# RTC_Miscellaneous.net
KiCad netlist of a schematic drawn in Altium Designer
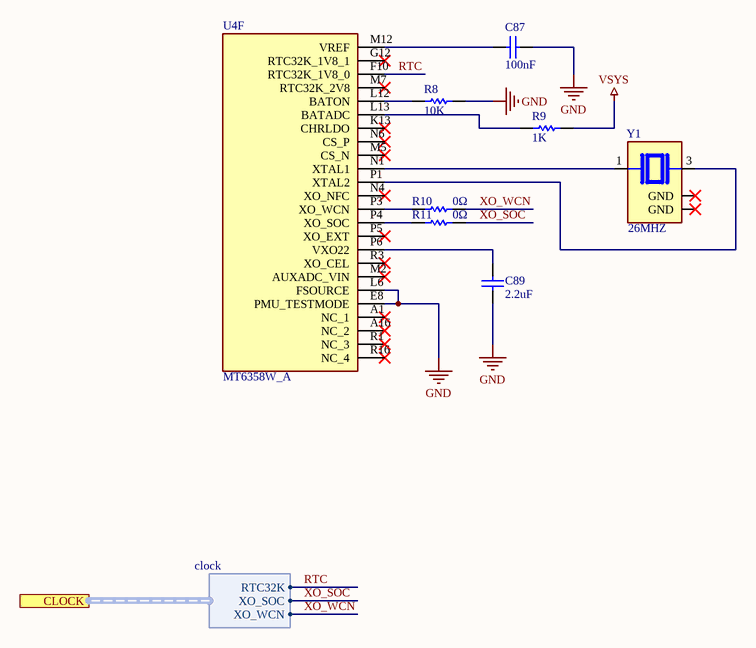
[diagram p0: RTC_Miscellaneous.SchDoc]

(export (version "E")
  (design (tool "Eeschema 10.0.6"))
  (components
    (comp (ref "C87")
      (value "100nF")
      (footprint "C0603")
      (fields (field (name "Comment") "C0603"))
      (libsource (lib "kit") (part "C0603"))
    )
    (comp (ref "C89")
      (value "2.2uF")
      (footprint "C0805")
      (fields (field (name "Comment") "C0805"))
      (libsource (lib "kit") (part "C0805"))
    )
    (comp (ref "R8")
      (value "10K")
      (footprint "R0603")
      (fields (field (name "Comment") "R0603"))
      (libsource (lib "kit") (part "R0603"))
    )
    (comp (ref "R9")
      (value "1K")
      (footprint "R0603")
      (fields (field (name "Comment") "R0603"))
      (libsource (lib "kit") (part "R0603"))
    )
    (comp (ref "R10")
      (value "0Ω")
      (footprint "R0603")
      (fields (field (name "Comment") "R0603"))
      (libsource (lib "kit") (part "R0603"))
    )
    (comp (ref "R11")
      (value "0Ω")
      (footprint "R0603")
      (fields (field (name "Comment") "R0603"))
      (libsource (lib "kit") (part "R0603"))
    )
    (comp (ref "U4")
      (value "MT6358W_A")
      (footprint "BGA194C40P16X15_640X600X66")
      (description "PMIC")
      (fields
        (field (name "MANUFACTURER_PART_NUMBER") "MT6358W/A")
        (field (name "MOUSER PART NUMBER") "840-MT6358W/A")
      )
      (libsource (lib "kit") (part "MT6358W_A"))
    )
    (comp (ref "Y1")
      (value "26MHZ")
      (footprint "OSCCC320X250X90N")
      (libsource (lib "kit") (part "NX3225GA-26MHZ-TI"))
    )
  )
  (nets
    (net (code "2") (name "/RTC") (class "Default")
      (node (ref "U4") (pin "F10") (pinfunction "RTC32K_1V8_0_F10") (pintype "passive"))
    )
    (net (code "3") (name "/XO_SOC") (class "Default")
      (node (ref "R11") (pin "2") (pinfunction "2_2") (pintype "passive"))
    )
    (net (code "4") (name "/XO_WCN") (class "Default")
      (node (ref "R10") (pin "2") (pinfunction "2_2") (pintype "passive"))
    )
    (net (code "6") (name "GND") (class "Default")
      (node (ref "C87") (pin "1") (pinfunction "1_1") (pintype "passive"))
      (node (ref "C89") (pin "1") (pinfunction "1_1") (pintype "passive"))
      (node (ref "R8") (pin "2") (pinfunction "2_2") (pintype "passive"))
      (node (ref "U4") (pin "E8") (pinfunction "PMU_TESTMODE_E8") (pintype "passive"))
      (node (ref "U4") (pin "L6") (pinfunction "FSOURCE_L6") (pintype "passive"))
    )
    (net (code "7") (name "Net-(U4F-BATADC)") (class "Default")
      (node (ref "R9") (pin "1") (pinfunction "1_1") (pintype "passive"))
      (node (ref "U4") (pin "L13") (pinfunction "BATADC_L13") (pintype "passive"))
    )
    (net (code "8") (name "Net-(U4F-BATON)") (class "Default")
      (node (ref "R8") (pin "1") (pinfunction "1_1") (pintype "passive"))
      (node (ref "U4") (pin "L12") (pinfunction "BATON_L12") (pintype "passive"))
    )
    (net (code "9") (name "Net-(U4F-VREF)") (class "Default")
      (node (ref "C87") (pin "2") (pinfunction "2_2") (pintype "passive"))
      (node (ref "U4") (pin "M12") (pinfunction "VREF_M12") (pintype "passive"))
    )
    (net (code "10") (name "Net-(U4F-VXO22)") (class "Default")
      (node (ref "C89") (pin "2") (pinfunction "2_2") (pintype "passive"))
      (node (ref "U4") (pin "P6") (pinfunction "VXO22_P6") (pintype "passive"))
    )
    (net (code "11") (name "Net-(U4F-XO_SOC)") (class "Default")
      (node (ref "R11") (pin "1") (pinfunction "1_1") (pintype "passive"))
      (node (ref "U4") (pin "P4") (pinfunction "XO_SOC_P4") (pintype "passive"))
    )
    (net (code "12") (name "Net-(U4F-XO_WCN)") (class "Default")
      (node (ref "R10") (pin "1") (pinfunction "1_1") (pintype "passive"))
      (node (ref "U4") (pin "P3") (pinfunction "XO_WCN_P3") (pintype "passive"))
    )
    (net (code "13") (name "Net-(U4F-XTAL1)") (class "Default")
      (node (ref "U4") (pin "N1") (pinfunction "XTAL1_N1") (pintype "passive"))
      (node (ref "Y1") (pin "1") (pinfunction "1_1") (pintype "passive"))
    )
    (net (code "14") (name "Net-(U4F-XTAL2)") (class "Default")
      (node (ref "U4") (pin "P1") (pinfunction "XTAL2_P1") (pintype "passive"))
      (node (ref "Y1") (pin "3") (pinfunction "3_3") (pintype "passive"))
    )
    (net (code "15") (name "VSYS") (class "Default")
      (node (ref "R9") (pin "2") (pinfunction "2_2") (pintype "passive"))
    )
    (net (code "16") (name "unconnected-(U4F-AUXADC_VIN-PadM2)") (class "Default")
      (node (ref "U4") (pin "M2") (pinfunction "AUXADC_VIN_M2") (pintype "passive+no_connect"))
    )
    (net (code "17") (name "unconnected-(U4F-CHRLDO-PadK13)") (class "Default")
      (node (ref "U4") (pin "K13") (pinfunction "CHRLDO_K13") (pintype "passive+no_connect"))
    )
    (net (code "18") (name "unconnected-(U4F-CS_N-PadM5)") (class "Default")
      (node (ref "U4") (pin "M5") (pinfunction "CS_N_M5") (pintype "passive+no_connect"))
    )
    (net (code "19") (name "unconnected-(U4F-CS_P-PadN6)") (class "Default")
      (node (ref "U4") (pin "N6") (pinfunction "CS_P_N6") (pintype "passive+no_connect"))
    )
    (net (code "20") (name "unconnected-(U4F-NC_1-PadA1)") (class "Default")
      (node (ref "U4") (pin "A1") (pinfunction "NC_1_A1") (pintype "passive+no_connect"))
    )
    (net (code "21") (name "unconnected-(U4F-NC_2-PadA16)") (class "Default")
      (node (ref "U4") (pin "A16") (pinfunction "NC_2_A16") (pintype "passive+no_connect"))
    )
    (net (code "22") (name "unconnected-(U4F-NC_3-PadR1)") (class "Default")
      (node (ref "U4") (pin "R1") (pinfunction "NC_3_R1") (pintype "passive+no_connect"))
    )
    (net (code "23") (name "unconnected-(U4F-NC_4-PadR16)") (class "Default")
      (node (ref "U4") (pin "R16") (pinfunction "NC_4_R16") (pintype "passive+no_connect"))
    )
    (net (code "24") (name "unconnected-(U4F-RTC32K_1V8_1-PadG12)") (class "Default")
      (node (ref "U4") (pin "G12") (pinfunction "RTC32K_1V8_1_G12") (pintype "passive+no_connect"))
    )
    (net (code "25") (name "unconnected-(U4F-RTC32K_2V8-PadM7)") (class "Default")
      (node (ref "U4") (pin "M7") (pinfunction "RTC32K_2V8_M7") (pintype "passive+no_connect"))
    )
    (net (code "26") (name "unconnected-(U4F-XO_CEL-PadR3)") (class "Default")
      (node (ref "U4") (pin "R3") (pinfunction "XO_CEL_R3") (pintype "passive+no_connect"))
    )
    (net (code "27") (name "unconnected-(U4F-XO_EXT-PadP5)") (class "Default")
      (node (ref "U4") (pin "P5") (pinfunction "XO_EXT_P5") (pintype "passive+no_connect"))
    )
    (net (code "28") (name "unconnected-(U4F-XO_NFC-PadN4)") (class "Default")
      (node (ref "U4") (pin "N4") (pinfunction "XO_NFC_N4") (pintype "passive+no_connect"))
    )
    (net (code "29") (name "unconnected-(Y1-GND-Pad2)") (class "Default")
      (node (ref "Y1") (pin "2") (pinfunction "GND_2") (pintype "power_in+no_connect"))
    )
    (net (code "30") (name "unconnected-(Y1-GND-Pad4)") (class "Default")
      (node (ref "Y1") (pin "4") (pinfunction "GND_4") (pintype "power_in+no_connect"))
    )
  )
)
